# SoundCastel.net
KiCad netlist of a schematic drawn in EAGLE
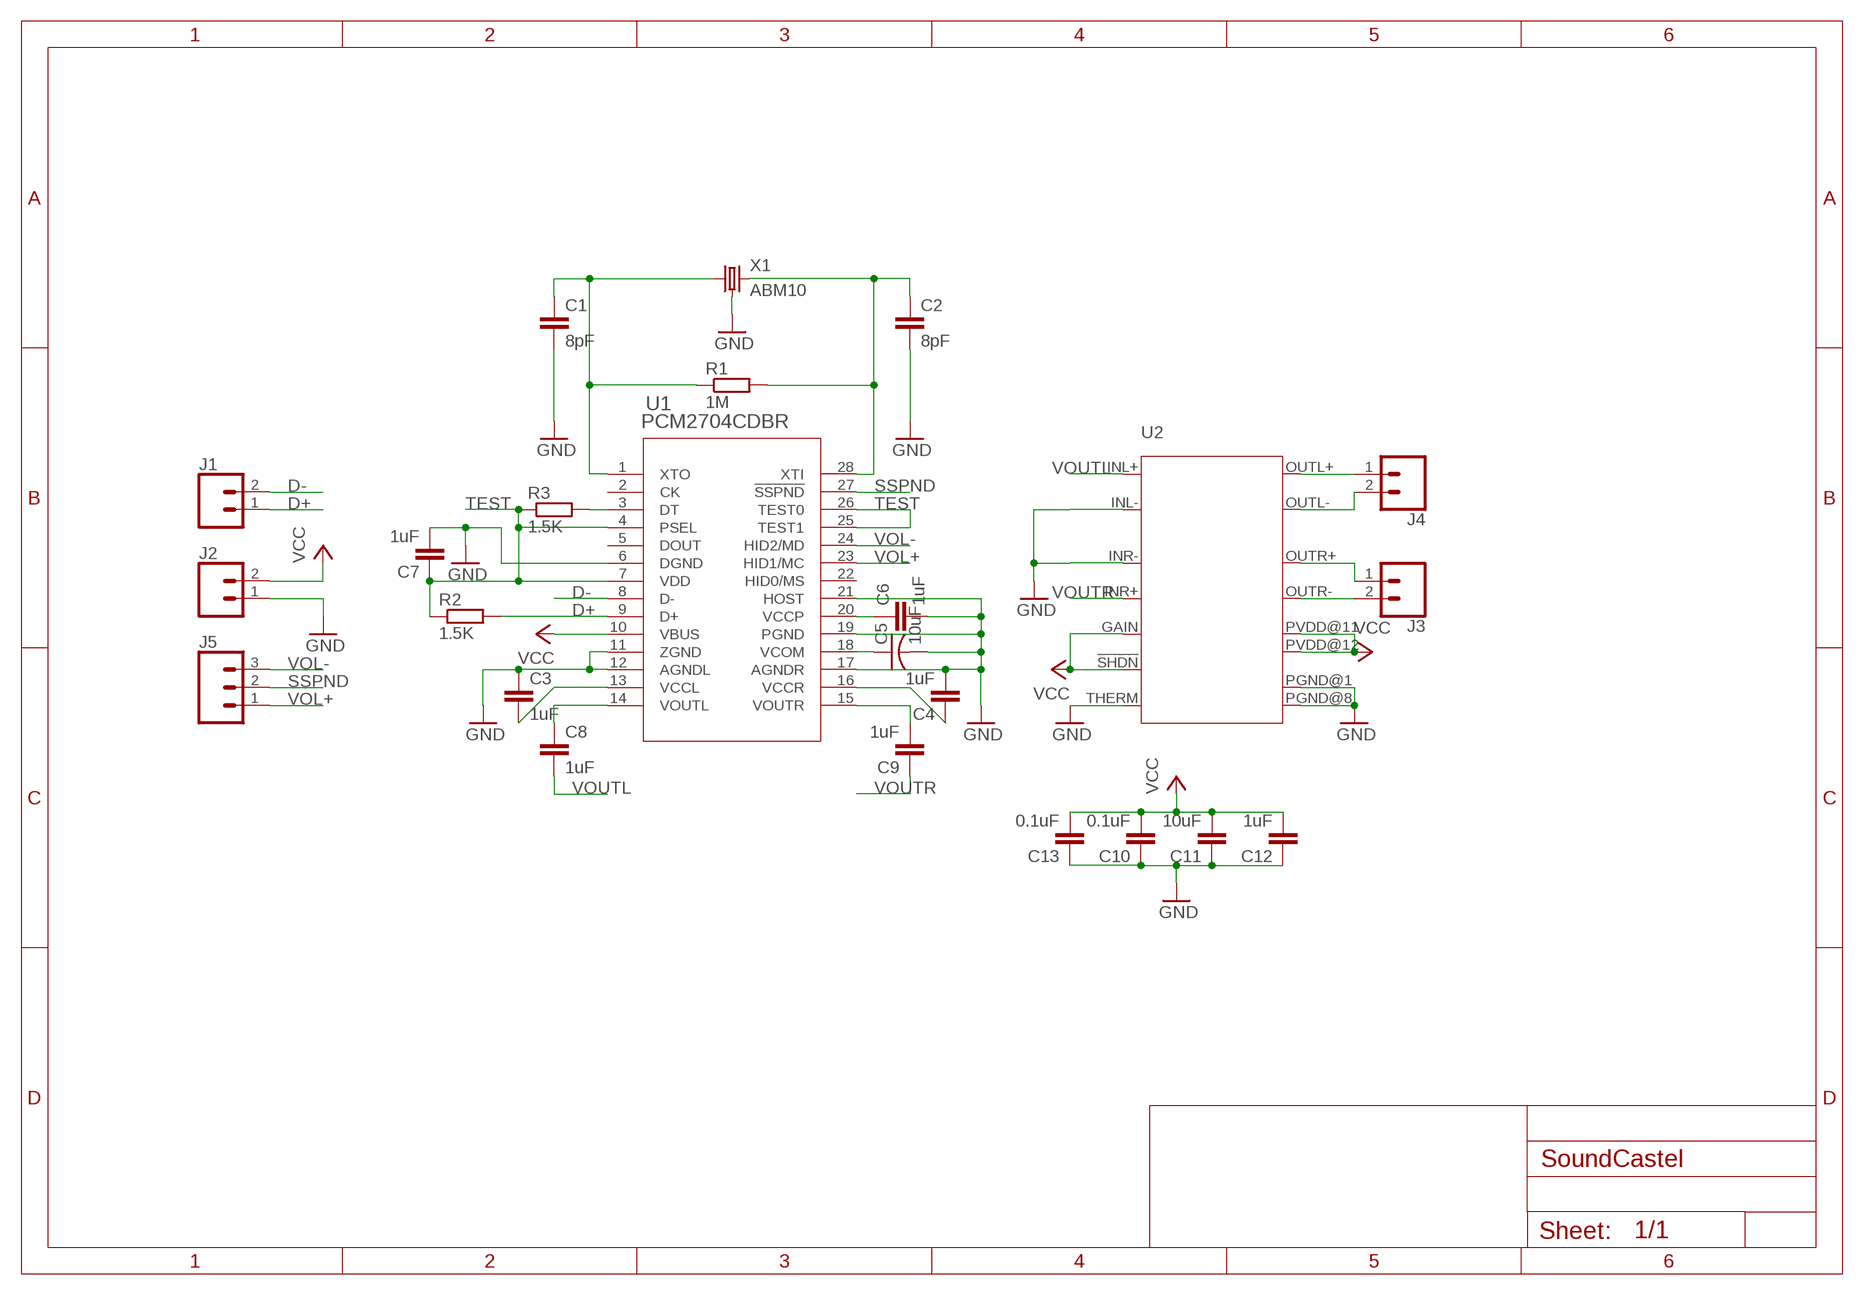
[diagram p0: schematic, sheet 1]

(export (version "E")
  (design (tool "Eeschema 10.0.6"))
  (components
    (comp (ref "C1")
      (value "8pF")
      (footprint "eagle-import:C0402")
      (libsource (lib "eagle-import") (part "C-EUC0402"))
    )
    (comp (ref "C2")
      (value "8pF")
      (footprint "eagle-import:C0402")
      (libsource (lib "eagle-import") (part "C-EUC0402"))
    )
    (comp (ref "C3")
      (value "1uF")
      (footprint "eagle-import:C0402")
      (libsource (lib "eagle-import") (part "C-EUC0402"))
    )
    (comp (ref "C4")
      (value "1uF")
      (footprint "eagle-import:C0402")
      (libsource (lib "eagle-import") (part "C-EUC0402"))
    )
    (comp (ref "C5")
      (value "10uF")
      (footprint "eagle-import:C0402")
      (libsource (lib "eagle-import") (part "C-USC0402"))
    )
    (comp (ref "C6")
      (value "1uF")
      (footprint "eagle-import:C0402")
      (libsource (lib "eagle-import") (part "C-EUC0402"))
    )
    (comp (ref "C7")
      (value "1uF")
      (footprint "eagle-import:C0402")
      (libsource (lib "eagle-import") (part "C-EUC0402"))
    )
    (comp (ref "C8")
      (value "1uF")
      (footprint "eagle-import:C0402")
      (libsource (lib "eagle-import") (part "C-EUC0402"))
    )
    (comp (ref "C9")
      (value "1uF")
      (footprint "eagle-import:C0402")
      (libsource (lib "eagle-import") (part "C-EUC0402"))
    )
    (comp (ref "C10")
      (value "0.1uF")
      (footprint "eagle-import:C0402")
      (libsource (lib "eagle-import") (part "C-EUC0402"))
    )
    (comp (ref "C11")
      (value "10uF")
      (footprint "eagle-import:C0402")
      (libsource (lib "eagle-import") (part "C-EUC0402"))
    )
    (comp (ref "C12")
      (value "1uF")
      (footprint "eagle-import:C0402")
      (libsource (lib "eagle-import") (part "C-EUC0402"))
    )
    (comp (ref "C13")
      (value "0.1uF")
      (footprint "eagle-import:C0402")
      (libsource (lib "eagle-import") (part "C-EUC0402"))
    )
    (comp (ref "J1")
      (value "CONN_021X02_NO_SILK")
      (footprint "eagle-import:1X02_NO_SILK")
      (libsource (lib "eagle-import") (part "CONN_021X02_NO_SILK"))
    )
    (comp (ref "J2")
      (value "CONN_021X02_NO_SILK")
      (footprint "eagle-import:1X02_NO_SILK")
      (libsource (lib "eagle-import") (part "CONN_021X02_NO_SILK"))
    )
    (comp (ref "J3")
      (value "CONN_021X02_NO_SILK")
      (footprint "eagle-import:1X02_NO_SILK")
      (libsource (lib "eagle-import") (part "CONN_021X02_NO_SILK"))
    )
    (comp (ref "J4")
      (value "CONN_021X02_NO_SILK")
      (footprint "eagle-import:1X02_NO_SILK")
      (libsource (lib "eagle-import") (part "CONN_021X02_NO_SILK"))
    )
    (comp (ref "J5")
      (value "CONN_031X03_NO_SILK")
      (footprint "eagle-import:1X03_NO_SILK")
      (libsource (lib "eagle-import") (part "CONN_031X03_NO_SILK"))
    )
    (comp (ref "R1")
      (value "1M")
      (footprint "eagle-import:R0402")
      (libsource (lib "eagle-import") (part "R-EU_R0402"))
    )
    (comp (ref "R2")
      (value "1.5K")
      (footprint "eagle-import:R0402")
      (libsource (lib "eagle-import") (part "R-EU_R0402"))
    )
    (comp (ref "R3")
      (value "1.5K")
      (footprint "eagle-import:R0402")
      (libsource (lib "eagle-import") (part "R-EU_R0402"))
    )
    (comp (ref "U1")
      (value "PCM2704CDBR")
      (footprint "eagle-import:DB28")
      (libsource (lib "eagle-import") (part "PCM2704CDBR"))
    )
    (comp (ref "U2")
      (value "MAX98306")
      (footprint "eagle-import:TDFN14")
      (libsource (lib "eagle-import") (part "MAX98306"))
    )
    (comp (ref "X1")
      (value "ABM10")
      (footprint "eagle-import:ABM10")
      (libsource (lib "eagle-import") (part "ABM10"))
    )
  )
  (nets
    (net (code "1") (name "/D+") (class "Default")
      (node (ref "J1") (pin "1") (pinfunction "1_1") (pintype "passive"))
      (node (ref "R2") (pin "2") (pinfunction "2_2") (pintype "passive"))
      (node (ref "U1") (pin "9") (pinfunction "D+_9") (pintype "bidirectional"))
    )
    (net (code "2") (name "/D-") (class "Default")
      (node (ref "J1") (pin "2") (pinfunction "2_2") (pintype "passive"))
      (node (ref "U1") (pin "8") (pinfunction "D-_8") (pintype "bidirectional"))
    )
    (net (code "3") (name "/SSPND") (class "Default")
      (node (ref "J5") (pin "2") (pinfunction "2_2") (pintype "passive"))
      (node (ref "U1") (pin "27") (pinfunction "~{SSPND}_27") (pintype "output"))
    )
    (net (code "4") (name "/TEST") (class "Default")
      (node (ref "C7") (pin "1") (pinfunction "1_1") (pintype "passive"))
      (node (ref "R2") (pin "1") (pinfunction "1_1") (pintype "passive"))
      (node (ref "R3") (pin "1") (pinfunction "1_1") (pintype "passive"))
      (node (ref "U1") (pin "25") (pinfunction "TEST1_25") (pintype "input"))
      (node (ref "U1") (pin "26") (pinfunction "TEST0_26") (pintype "input"))
      (node (ref "U1") (pin "4") (pinfunction "PSEL_4") (pintype "input"))
      (node (ref "U1") (pin "7") (pinfunction "VDD_7") (pintype "power_in"))
    )
    (net (code "5") (name "/VOL+") (class "Default")
      (node (ref "J5") (pin "1") (pinfunction "1_1") (pintype "passive"))
      (node (ref "U1") (pin "23") (pinfunction "HID1/MC_23") (pintype "input"))
    )
    (net (code "6") (name "/VOL-") (class "Default")
      (node (ref "J5") (pin "3") (pinfunction "3_3") (pintype "passive"))
      (node (ref "U1") (pin "24") (pinfunction "HID2/MD_24") (pintype "input"))
    )
    (net (code "7") (name "/VOUTL") (class "Default")
      (node (ref "C8") (pin "2") (pinfunction "2_2") (pintype "passive"))
      (node (ref "U2") (pin "INL+") (pinfunction "3_INL+") (pintype "bidirectional"))
    )
    (net (code "8") (name "/VOUTR") (class "Default")
      (node (ref "C9") (pin "1") (pinfunction "1_1") (pintype "passive"))
      (node (ref "U2") (pin "INR+") (pinfunction "6_INR+") (pintype "bidirectional"))
    )
    (net (code "9") (name "GND") (class "Default")
      (node (ref "C1") (pin "2") (pinfunction "2_2") (pintype "passive"))
      (node (ref "C10") (pin "1") (pinfunction "1_1") (pintype "passive"))
      (node (ref "C11") (pin "1") (pinfunction "1_1") (pintype "passive"))
      (node (ref "C12") (pin "1") (pinfunction "1_1") (pintype "passive"))
      (node (ref "C13") (pin "1") (pinfunction "1_1") (pintype "passive"))
      (node (ref "C2") (pin "2") (pinfunction "2_2") (pintype "passive"))
      (node (ref "C3") (pin "1") (pinfunction "1_1") (pintype "passive"))
      (node (ref "C4") (pin "2") (pinfunction "2_2") (pintype "passive"))
      (node (ref "C5") (pin "2") (pinfunction "2_2") (pintype "passive"))
      (node (ref "C6") (pin "2") (pinfunction "2_2") (pintype "passive"))
      (node (ref "C7") (pin "2") (pinfunction "2_2") (pintype "passive"))
      (node (ref "J2") (pin "1") (pinfunction "1_1") (pintype "passive"))
      (node (ref "U1") (pin "11") (pinfunction "ZGND_11") (pintype "power_in"))
      (node (ref "U1") (pin "12") (pinfunction "AGNDL_12") (pintype "power_in"))
      (node (ref "U1") (pin "17") (pinfunction "AGNDR_17") (pintype "power_in"))
      (node (ref "U1") (pin "19") (pinfunction "PGND_19") (pintype "power_in"))
      (node (ref "U1") (pin "21") (pinfunction "HOST_21") (pintype "input"))
      (node (ref "U1") (pin "6") (pinfunction "DGND_6") (pintype "power_in"))
      (node (ref "U2") (pin "INL-") (pinfunction "4_INL-") (pintype "bidirectional"))
      (node (ref "U2") (pin "INR-") (pinfunction "7_INR-") (pintype "bidirectional"))
      (node (ref "U2") (pin "PGND@1") (pinfunction "1_PGND@1") (pintype "bidirectional"))
      (node (ref "U2") (pin "PGND@8") (pinfunction "8_PGND@8") (pintype "bidirectional"))
      (node (ref "U2") (pin "THERM") (pinfunction "THERMAL_THERM") (pintype "bidirectional"))
      (node (ref "X1") (pin "2") (pinfunction "3_2") (pintype "bidirectional"))
      (node (ref "X1") (pin "4") (pinfunction "3_4") (pintype "bidirectional"))
    )
    (net (code "10") (name "Net-(U1-DT)") (class "Default")
      (node (ref "R3") (pin "2") (pinfunction "2_2") (pintype "passive"))
      (node (ref "U1") (pin "3") (pinfunction "DT_3") (pintype "bidirectional"))
    )
    (net (code "11") (name "Net-(U1-VCCL)") (class "Default")
      (node (ref "C3") (pin "2") (pinfunction "2_2") (pintype "passive"))
      (node (ref "U1") (pin "13") (pinfunction "VCCL_13") (pintype "power_in"))
    )
    (net (code "12") (name "Net-(U1-VCCP)") (class "Default")
      (node (ref "C6") (pin "1") (pinfunction "1_1") (pintype "passive"))
      (node (ref "U1") (pin "20") (pinfunction "VCCP_20") (pintype "power_in"))
    )
    (net (code "13") (name "Net-(U1-VCCR)") (class "Default")
      (node (ref "C4") (pin "1") (pinfunction "1_1") (pintype "passive"))
      (node (ref "U1") (pin "16") (pinfunction "VCCR_16") (pintype "power_in"))
    )
    (net (code "14") (name "Net-(U1-VCOM)") (class "Default")
      (node (ref "C5") (pin "1") (pinfunction "1_1") (pintype "passive"))
      (node (ref "U1") (pin "18") (pinfunction "VCOM_18") (pintype "power_in"))
    )
    (net (code "15") (name "Net-(U1-VOUTL)") (class "Default")
      (node (ref "C8") (pin "1") (pinfunction "1_1") (pintype "passive"))
      (node (ref "U1") (pin "14") (pinfunction "VOUTL_14") (pintype "output"))
    )
    (net (code "16") (name "Net-(U1-VOUTR)") (class "Default")
      (node (ref "C9") (pin "2") (pinfunction "2_2") (pintype "passive"))
      (node (ref "U1") (pin "15") (pinfunction "VOUTR_15") (pintype "output"))
    )
    (net (code "17") (name "Net-(U1-XTI)") (class "Default")
      (node (ref "C2") (pin "1") (pinfunction "1_1") (pintype "passive"))
      (node (ref "R1") (pin "2") (pinfunction "2_2") (pintype "passive"))
      (node (ref "U1") (pin "28") (pinfunction "XTI_28") (pintype "input"))
      (node (ref "X1") (pin "3") (pinfunction "2_3") (pintype "passive"))
    )
    (net (code "18") (name "Net-(U1-XTO)") (class "Default")
      (node (ref "C1") (pin "1") (pinfunction "1_1") (pintype "passive"))
      (node (ref "R1") (pin "1") (pinfunction "1_1") (pintype "passive"))
      (node (ref "U1") (pin "1") (pinfunction "XTO_1") (pintype "output"))
      (node (ref "X1") (pin "1") (pinfunction "1_1") (pintype "passive"))
    )
    (net (code "19") (name "Net-(U2-9)") (class "Default")
      (node (ref "J3") (pin "2") (pinfunction "2_2") (pintype "passive"))
      (node (ref "U2") (pin "OUTR-") (pinfunction "9_OUTR-") (pintype "bidirectional"))
    )
    (net (code "20") (name "Net-(U2-10)") (class "Default")
      (node (ref "J3") (pin "1") (pinfunction "1_1") (pintype "passive"))
      (node (ref "U2") (pin "OUTR+") (pinfunction "10_OUTR+") (pintype "bidirectional"))
    )
    (net (code "21") (name "Net-(U2-13)") (class "Default")
      (node (ref "J4") (pin "1") (pinfunction "1_1") (pintype "passive"))
      (node (ref "U2") (pin "OUTL+") (pinfunction "13_OUTL+") (pintype "bidirectional"))
    )
    (net (code "22") (name "Net-(U2-14)") (class "Default")
      (node (ref "J4") (pin "2") (pinfunction "2_2") (pintype "passive"))
      (node (ref "U2") (pin "OUTL-") (pinfunction "14_OUTL-") (pintype "bidirectional"))
    )
    (net (code "23") (name "VCC") (class "Default")
      (node (ref "C10") (pin "2") (pinfunction "2_2") (pintype "passive"))
      (node (ref "C11") (pin "2") (pinfunction "2_2") (pintype "passive"))
      (node (ref "C12") (pin "2") (pinfunction "2_2") (pintype "passive"))
      (node (ref "C13") (pin "2") (pinfunction "2_2") (pintype "passive"))
      (node (ref "J2") (pin "2") (pinfunction "2_2") (pintype "passive"))
      (node (ref "U1") (pin "10") (pinfunction "VBUS_10") (pintype "power_in"))
      (node (ref "U2") (pin "!SHDN") (pinfunction "2_!SHDN") (pintype "bidirectional"))
      (node (ref "U2") (pin "GAIN") (pinfunction "5_GAIN") (pintype "bidirectional"))
      (node (ref "U2") (pin "PVDD@11") (pinfunction "11_PVDD@11") (pintype "bidirectional"))
      (node (ref "U2") (pin "PVDD@12") (pinfunction "12_PVDD@12") (pintype "bidirectional"))
    )
    (net (code "24") (name "unconnected-(U1-CK-Pad2)") (class "Default")
      (node (ref "U1") (pin "2") (pinfunction "CK_2") (pintype "output"))
    )
    (net (code "25") (name "unconnected-(U1-DOUT-Pad5)") (class "Default")
      (node (ref "U1") (pin "5") (pinfunction "DOUT_5") (pintype "output"))
    )
    (net (code "26") (name "unconnected-(U1-HID0{slash}MS-Pad22)") (class "Default")
      (node (ref "U1") (pin "22") (pinfunction "HID0/MS_22") (pintype "input"))
    )
  )
)
